# 06_Arduino_UNO.net
KiCad netlist of a schematic drawn in Altium Designer
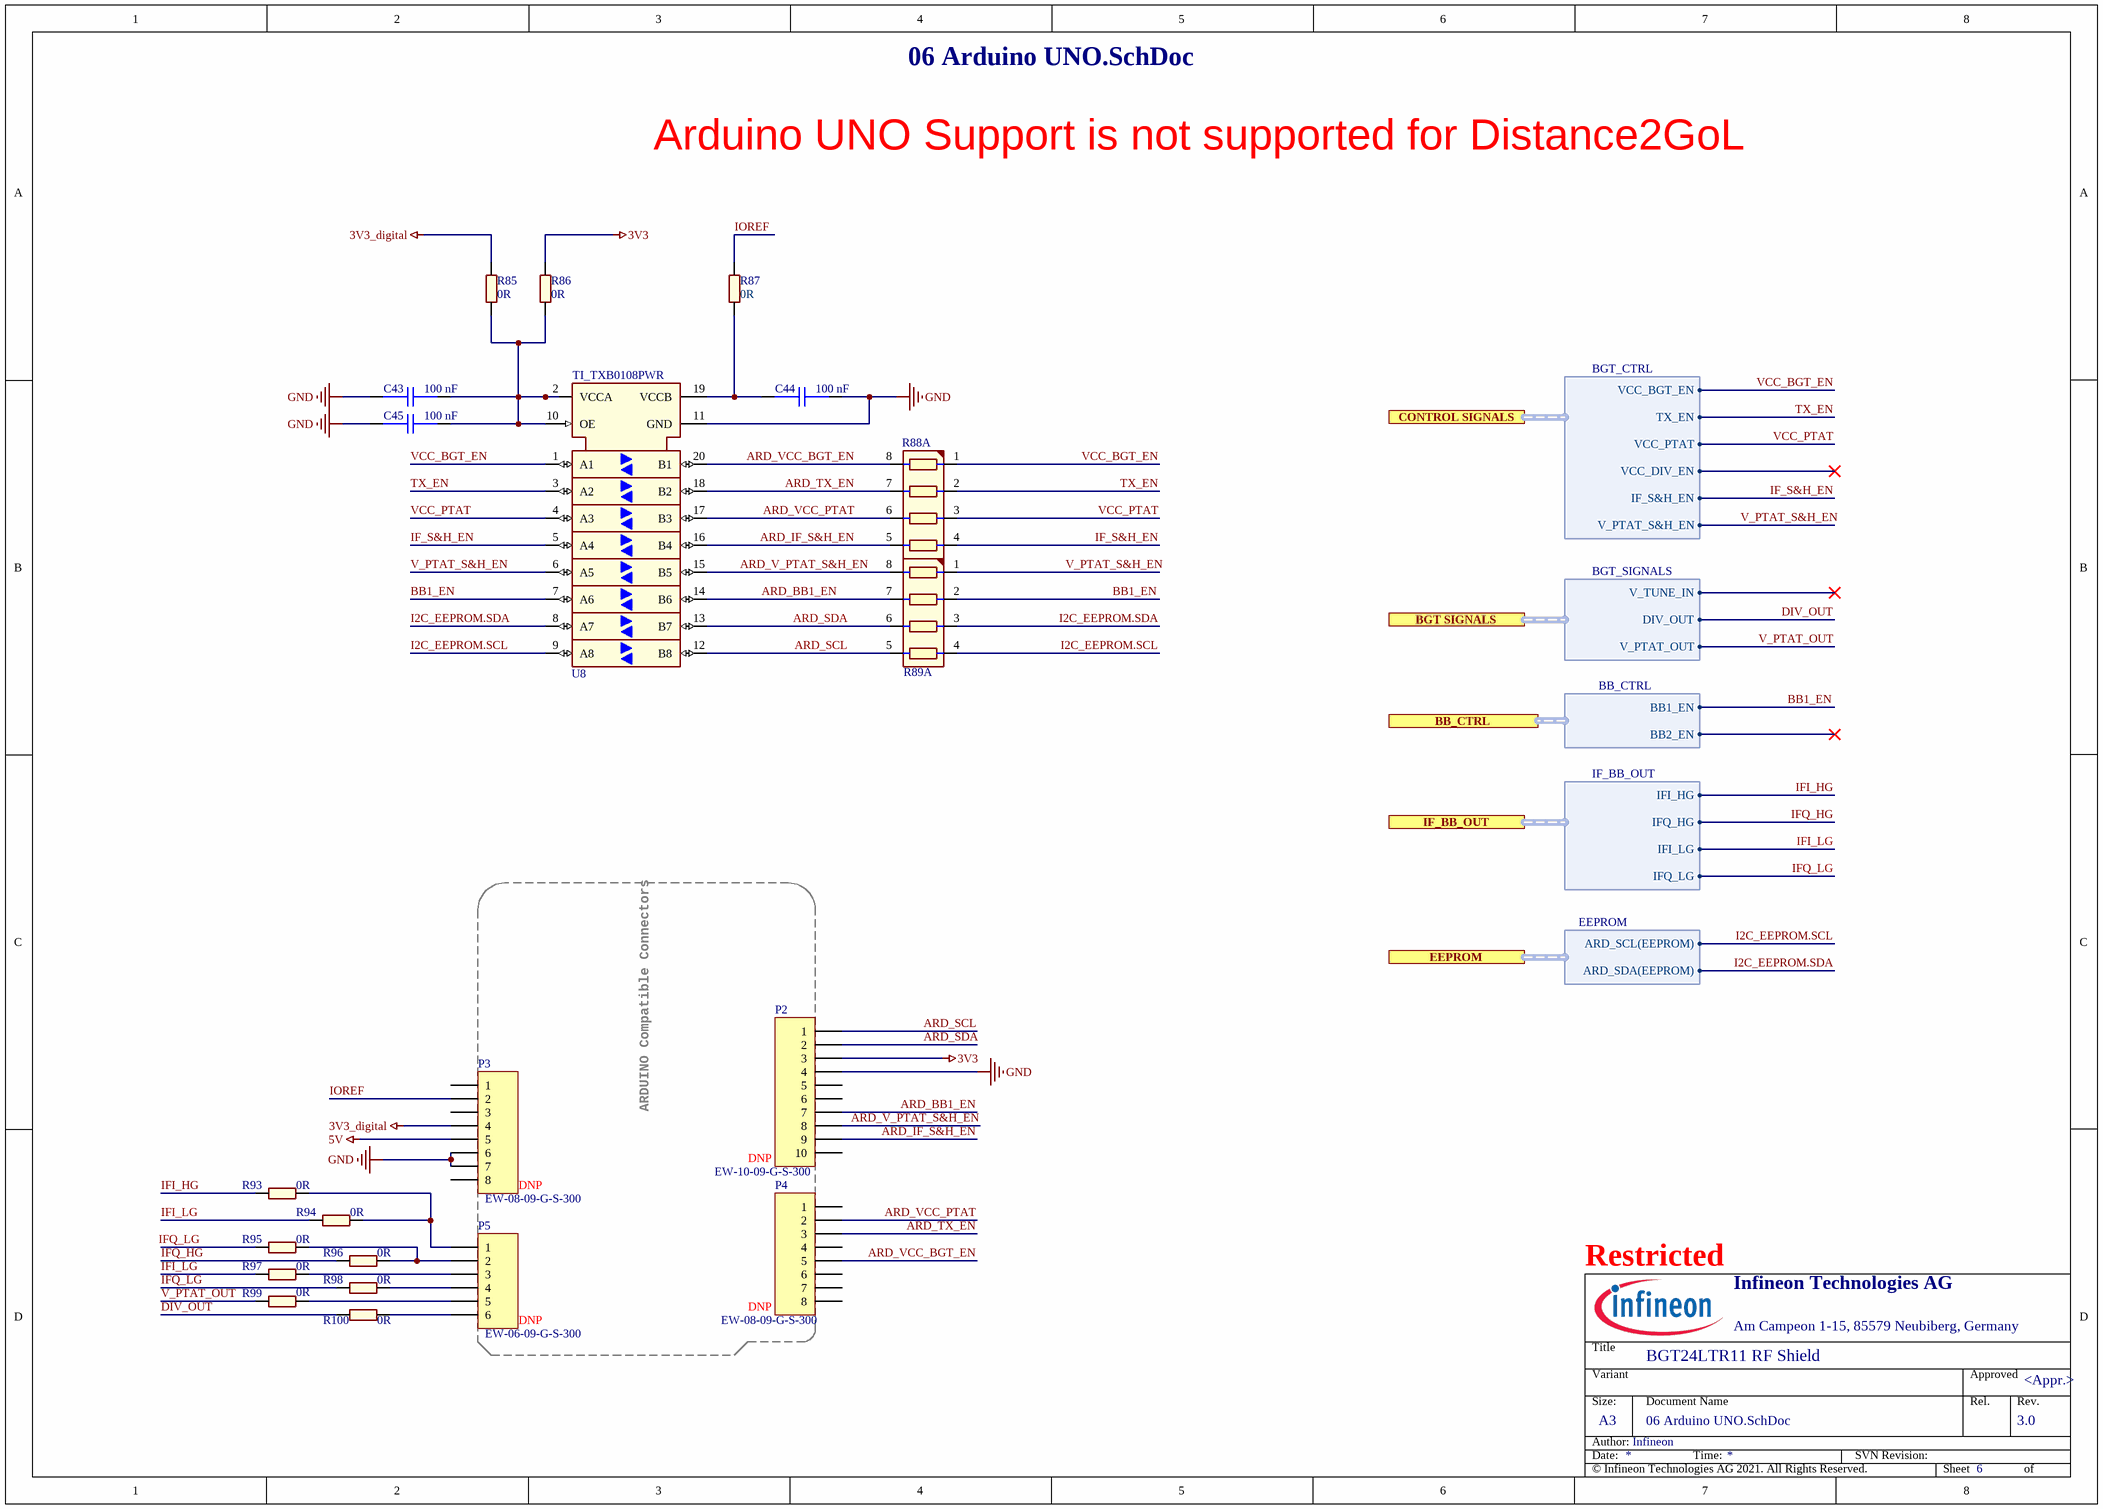
[diagram p0: 06 Arduino UNO.SchDoc]

(export (version "E")
  (design (tool "Eeschema 10.0.6"))
  (components
    (comp (ref "C43")
      (value "100 nF")
      (footprint "CAPC1005X55N-0_2")
      (description "General Purpose Surface Mount Ceramic Capacitor")
      (fields (field (name "PARTNUMBER") "CAP01010597") (field (name "VOLTAGE") "16Vdc"))
      (libsource (lib "DB_External_Capacitor") (part "c_std_a"))
    )
    (comp (ref "C44")
      (value "100 nF")
      (footprint "CAPC1005X55N-0_2")
      (description "General Purpose Surface Mount Ceramic Capacitor")
      (fields (field (name "PARTNUMBER") "CAP01010597") (field (name "VOLTAGE") "16Vdc"))
      (libsource (lib "DB_External_Capacitor") (part "c_std_a"))
    )
    (comp (ref "C45")
      (value "100 nF")
      (footprint "CAPC1005X55N-0_2")
      (description "General Purpose Surface Mount Ceramic Capacitor")
      (fields (field (name "PARTNUMBER") "CAP01010597") (field (name "VOLTAGE") "16Vdc"))
      (libsource (lib "DB_External_Capacitor") (part "c_std_a"))
    )
    (comp (ref "P2")
      (value "DNP")
      (footprint "HDR1X10_Plug - DNP")
      (description "Header, 10-Pin, 10mm Height, EW-10-09-G-S-300")
      (fields
        (field (name "MANUFACTURER PART NUMBER") "EW-10-09-G-S-300")
        (field (name "MANUFACTURER") "Samtec")
        (field (name "PUBLISHER") "Altium Limited")
      )
      (libsource (lib "Miscellaneous Connectors") (part "Header 10"))
    )
    (comp (ref "P3")
      (value "DNP")
      (footprint "HDR1X8_Plug - DNP")
      (description "Header, 8-Pin 10mm Height, EW-08-09-G-S-300")
      (fields
        (field (name "MANUFACTURER PART NUMBER") "EW-08-09-G-S-300")
        (field (name "MANUFACTURER") "Samtec")
        (field (name "PUBLISHER") "Altium Limited")
      )
      (libsource (lib "") (part "Header 8_1"))
    )
    (comp (ref "P4")
      (value "DNP")
      (footprint "HDR1X8_Plug - DNP")
      (description "Header, 8-Pin 10mm Height, EW-08-09-G-S-300")
      (fields
        (field (name "MANUFACTURER PART NUMBER") "EW-08-09-G-S-300")
        (field (name "MANUFACTURER") "Samtec")
        (field (name "PUBLISHER") "Altium Limited")
      )
      (libsource (lib "Miscellaneous Connectors") (part "Header 8"))
    )
    (comp (ref "P5")
      (value "DNP")
      (footprint "HDR1X6_Plug - DNP")
      (description "Header, 6-Pin, 10mm Height, EW-06-09-G-S-300")
      (fields
        (field (name "MANUFACTURER PART NUMBER") "EW-06-09-G-S-300")
        (field (name "MANUFACTURER") "Samtec")
        (field (name "PUBLISHER") "Altium Limited")
      )
      (libsource (lib "Miscellaneous Connectors") (part "Header 6"))
    )
    (comp (ref "R85")
      (value "0R")
      (footprint "RESC1005X40N_2")
      (description "0R/50V/20mOhm")
      (fields (field (name "PARTNUMBER") "RES01800000") (field (name "POWER") "1.5A"))
      (libsource (lib "") (part "r_std_a_2"))
    )
    (comp (ref "R86")
      (value "0R")
      (footprint "RESC1005X40N_2")
      (description "0R/50V/20mOhm")
      (fields (field (name "PARTNUMBER") "RES01800000") (field (name "POWER") "1.5A"))
      (libsource (lib "") (part "r_std_a_3"))
    )
    (comp (ref "R87")
      (value "0R")
      (footprint "RESC1005X40N_2")
      (description "0R/50V/20mOhm")
      (fields (field (name "PARTNUMBER") "RES01800000") (field (name "POWER") "1.5A"))
      (libsource (lib "") (part "r_std_a_3"))
    )
    (comp (ref "R88")
      (value "DNP")
      (footprint "RESCAX50P100X200X45-8N - DNP")
      (description "Thick Film Chip Resistor Array")
      (fields (field (name "MANUFACTURER") "Panasonic"))
      (libsource (lib "BGT24LTR11 RF-Shield Board V0.2") (part "RES-ARY-STD-08P_00000029"))
    )
    (comp (ref "R89")
      (value "DNP")
      (footprint "RESCAX50P100X200X45-8N - DNP")
      (description "Thick Film Chip Resistor Array")
      (fields (field (name "MANUFACTURER") "Panasonic"))
      (libsource (lib "BGT24LTR11 RF-Shield Board V0.2") (part "RES-ARY-STD-08P_00000029"))
    )
    (comp (ref "R93")
      (value "0R")
      (footprint "RESC1005X40N_2")
      (description "0R/50V/20mOhm")
      (fields (field (name "PARTNUMBER") "RES01800000") (field (name "POWER") "1.5A"))
      (libsource (lib "DB_External_Resistor") (part "r_std_a"))
    )
    (comp (ref "R94")
      (value "0R")
      (footprint "RESC1005X40N_2")
      (description "0R/50V/20mOhm")
      (fields (field (name "PARTNUMBER") "RES01800000") (field (name "POWER") "1.5A"))
      (libsource (lib "DB_External_Resistor") (part "r_std_a"))
    )
    (comp (ref "R95")
      (value "0R")
      (footprint "RESC1005X40N_2")
      (description "0R/50V/20mOhm")
      (fields (field (name "PARTNUMBER") "RES01800000") (field (name "POWER") "1.5A"))
      (libsource (lib "DB_External_Resistor") (part "r_std_a"))
    )
    (comp (ref "R96")
      (value "0R")
      (footprint "RESC1005X40N_2")
      (description "0R/50V/20mOhm")
      (fields (field (name "PARTNUMBER") "RES01800000") (field (name "POWER") "1.5A"))
      (libsource (lib "DB_External_Resistor") (part "r_std_a"))
    )
    (comp (ref "R97")
      (value "0R")
      (footprint "RESC1005X40N_2")
      (description "0R/50V/20mOhm")
      (fields (field (name "PARTNUMBER") "RES01800000") (field (name "POWER") "1.5A"))
      (libsource (lib "DB_External_Resistor") (part "r_std_a"))
    )
    (comp (ref "R98")
      (value "0R")
      (footprint "RESC1005X40N_2")
      (description "0R/50V/20mOhm")
      (fields (field (name "PARTNUMBER") "RES01800000") (field (name "POWER") "1.5A"))
      (libsource (lib "DB_External_Resistor") (part "r_std_a"))
    )
    (comp (ref "R99")
      (value "0R")
      (footprint "RESC1005X40N_2")
      (description "0R/50V/20mOhm")
      (fields (field (name "PARTNUMBER") "RES01800000") (field (name "POWER") "1.5A"))
      (libsource (lib "DB_External_Resistor") (part "r_std_a"))
    )
    (comp (ref "R100")
      (value "0R")
      (footprint "RESC1005X40N_2")
      (description "0R/50V/20mOhm")
      (fields (field (name "PARTNUMBER") "RES01800000") (field (name "POWER") "1.5A"))
      (libsource (lib "") (part "r_std_a_1"))
    )
    (comp (ref "U8")
      (value "DNP")
      (footprint "SOP65P640X120-20N - DNP")
      (description "TI_TXB0108PWR")
      (fields
        (field (name "PARTNUMBER") "IC02600537")
        (field (name "COMPONENTNAME") "TI_TXB0108PWR")
        (field (name "MANUFACTURERPARTNUMBER") "TXB0108PWR")
      )
      (libsource (lib "DB_External_IC") (part "TXB0108PWR"))
    )
  )
  (nets
    (net (code "6") (name "/ARD_BB1_EN") (class "Default")
      (node (ref "P2") (pin "7") (pinfunction "7_7") (pintype "passive"))
      (node (ref "R89") (pin "7") (pinfunction "7_7") (pintype "passive"))
      (node (ref "U8") (pin "14") (pinfunction "B6_14") (pintype "bidirectional"))
    )
    (net (code "7") (name "/ARD_IF_S&H_EN") (class "Default")
      (node (ref "P2") (pin "9") (pinfunction "9_9") (pintype "passive"))
      (node (ref "R88") (pin "5") (pinfunction "5_5") (pintype "passive"))
      (node (ref "U8") (pin "16") (pinfunction "B4_16") (pintype "bidirectional"))
    )
    (net (code "8") (name "/ARD_SCL") (class "Default")
      (node (ref "P2") (pin "1") (pinfunction "1_1") (pintype "passive"))
      (node (ref "R89") (pin "5") (pinfunction "5_5") (pintype "passive"))
      (node (ref "U8") (pin "12") (pinfunction "B8_12") (pintype "bidirectional"))
    )
    (net (code "9") (name "/ARD_SDA") (class "Default")
      (node (ref "P2") (pin "2") (pinfunction "2_2") (pintype "passive"))
      (node (ref "R89") (pin "6") (pinfunction "6_6") (pintype "passive"))
      (node (ref "U8") (pin "13") (pinfunction "B7_13") (pintype "bidirectional"))
    )
    (net (code "10") (name "/ARD_TX_EN") (class "Default")
      (node (ref "P4") (pin "3") (pinfunction "3_3") (pintype "passive"))
      (node (ref "R88") (pin "7") (pinfunction "7_7") (pintype "passive"))
      (node (ref "U8") (pin "18") (pinfunction "B2_18") (pintype "bidirectional"))
    )
    (net (code "11") (name "/ARD_VCC_BGT_EN") (class "Default")
      (node (ref "P4") (pin "5") (pinfunction "5_5") (pintype "passive"))
      (node (ref "R88") (pin "8") (pinfunction "8_8") (pintype "passive"))
      (node (ref "U8") (pin "20") (pinfunction "B1_20") (pintype "bidirectional"))
    )
    (net (code "12") (name "/ARD_VCC_PTAT") (class "Default")
      (node (ref "P4") (pin "2") (pinfunction "2_2") (pintype "passive"))
      (node (ref "R88") (pin "6") (pinfunction "6_6") (pintype "passive"))
      (node (ref "U8") (pin "17") (pinfunction "B3_17") (pintype "bidirectional"))
    )
    (net (code "13") (name "/ARD_V_PTAT_S&H_EN") (class "Default")
      (node (ref "P2") (pin "8") (pinfunction "8_8") (pintype "passive"))
      (node (ref "R89") (pin "8") (pinfunction "8_8") (pintype "passive"))
      (node (ref "U8") (pin "15") (pinfunction "B5_15") (pintype "bidirectional"))
    )
    (net (code "14") (name "/BB1_EN") (class "Default")
      (node (ref "R89") (pin "2") (pinfunction "2_2") (pintype "passive"))
      (node (ref "U8") (pin "7") (pinfunction "A6_7") (pintype "bidirectional"))
    )
    (net (code "15") (name "/DIV_OUT") (class "Default")
      (node (ref "R100") (pin "2") (pinfunction "2_2") (pintype "passive"))
    )
    (net (code "16") (name "/I2C_EEPROM.SCL") (class "Default")
      (node (ref "R89") (pin "4") (pinfunction "4_4") (pintype "passive"))
      (node (ref "U8") (pin "9") (pinfunction "A8_9") (pintype "bidirectional"))
    )
    (net (code "17") (name "/I2C_EEPROM.SDA") (class "Default")
      (node (ref "R89") (pin "3") (pinfunction "3_3") (pintype "passive"))
      (node (ref "U8") (pin "8") (pinfunction "A7_8") (pintype "bidirectional"))
    )
    (net (code "18") (name "/IFI_HG") (class "Default")
      (node (ref "R93") (pin "2") (pinfunction "2_2") (pintype "passive"))
    )
    (net (code "19") (name "/IFI_LG") (class "Default")
      (node (ref "R94") (pin "2") (pinfunction "2_2") (pintype "passive"))
      (node (ref "R97") (pin "2") (pinfunction "2_2") (pintype "passive"))
    )
    (net (code "20") (name "/IFQ_HG") (class "Default")
      (node (ref "R96") (pin "2") (pinfunction "2_2") (pintype "passive"))
    )
    (net (code "21") (name "/IFQ_LG") (class "Default")
      (node (ref "R95") (pin "2") (pinfunction "2_2") (pintype "passive"))
      (node (ref "R98") (pin "2") (pinfunction "2_2") (pintype "passive"))
    )
    (net (code "22") (name "/IF_S&H_EN") (class "Default")
      (node (ref "R88") (pin "4") (pinfunction "4_4") (pintype "passive"))
      (node (ref "U8") (pin "5") (pinfunction "A4_5") (pintype "bidirectional"))
    )
    (net (code "23") (name "/IOREF") (class "Default")
      (node (ref "P3") (pin "2") (pinfunction "2_2") (pintype "passive"))
      (node (ref "R87") (pin "2") (pinfunction "2_2") (pintype "passive"))
    )
    (net (code "24") (name "/TX_EN") (class "Default")
      (node (ref "R88") (pin "2") (pinfunction "2_2") (pintype "passive"))
      (node (ref "U8") (pin "3") (pinfunction "A2_3") (pintype "bidirectional"))
    )
    (net (code "25") (name "/VCC_BGT_EN") (class "Default")
      (node (ref "R88") (pin "1") (pinfunction "1_1") (pintype "passive"))
      (node (ref "U8") (pin "1") (pinfunction "A1_1") (pintype "bidirectional"))
    )
    (net (code "26") (name "/VCC_PTAT") (class "Default")
      (node (ref "R88") (pin "3") (pinfunction "3_3") (pintype "passive"))
      (node (ref "U8") (pin "4") (pinfunction "A3_4") (pintype "bidirectional"))
    )
    (net (code "27") (name "/V_PTAT_OUT") (class "Default")
      (node (ref "R99") (pin "2") (pinfunction "2_2") (pintype "passive"))
    )
    (net (code "28") (name "/V_PTAT_S&H_EN") (class "Default")
      (node (ref "R89") (pin "1") (pinfunction "1_1") (pintype "passive"))
      (node (ref "U8") (pin "6") (pinfunction "A5_6") (pintype "bidirectional"))
    )
    (net (code "34") (name "3V3") (class "Default")
      (node (ref "P2") (pin "3") (pinfunction "3_3") (pintype "passive"))
      (node (ref "R86") (pin "2") (pinfunction "2_2") (pintype "passive"))
    )
    (net (code "35") (name "3V3_digital") (class "Default")
      (node (ref "P3") (pin "4") (pinfunction "4_4") (pintype "passive"))
      (node (ref "R85") (pin "2") (pinfunction "2_2") (pintype "passive"))
    )
    (net (code "36") (name "5V") (class "Default")
      (node (ref "P3") (pin "5") (pinfunction "5_5") (pintype "passive"))
    )
    (net (code "37") (name "GND") (class "Default")
      (node (ref "C43") (pin "1") (pinfunction "1_1") (pintype "passive"))
      (node (ref "C44") (pin "2") (pinfunction "2_2") (pintype "passive"))
      (node (ref "C45") (pin "1") (pinfunction "1_1") (pintype "passive"))
      (node (ref "P2") (pin "4") (pinfunction "4_4") (pintype "passive"))
      (node (ref "P3") (pin "6") (pinfunction "6_6") (pintype "passive"))
      (node (ref "P3") (pin "7") (pinfunction "7_7") (pintype "passive"))
      (node (ref "U8") (pin "11") (pinfunction "GND_11") (pintype "power_in"))
    )
    (net (code "38") (name "Net-(P5-Pad1)") (class "Default")
      (node (ref "P5") (pin "1") (pinfunction "1_1") (pintype "passive"))
      (node (ref "R93") (pin "1") (pinfunction "1_1") (pintype "passive"))
      (node (ref "R94") (pin "1") (pinfunction "1_1") (pintype "passive"))
    )
    (net (code "39") (name "Net-(P5-Pad2)") (class "Default")
      (node (ref "P5") (pin "2") (pinfunction "2_2") (pintype "passive"))
      (node (ref "R95") (pin "1") (pinfunction "1_1") (pintype "passive"))
      (node (ref "R96") (pin "1") (pinfunction "1_1") (pintype "passive"))
    )
    (net (code "40") (name "Net-(P5-Pad3)") (class "Default")
      (node (ref "P5") (pin "3") (pinfunction "3_3") (pintype "passive"))
      (node (ref "R97") (pin "1") (pinfunction "1_1") (pintype "passive"))
    )
    (net (code "41") (name "Net-(P5-Pad4)") (class "Default")
      (node (ref "P5") (pin "4") (pinfunction "4_4") (pintype "passive"))
      (node (ref "R98") (pin "1") (pinfunction "1_1") (pintype "passive"))
    )
    (net (code "42") (name "Net-(P5-Pad5)") (class "Default")
      (node (ref "P5") (pin "5") (pinfunction "5_5") (pintype "passive"))
      (node (ref "R99") (pin "1") (pinfunction "1_1") (pintype "passive"))
    )
    (net (code "43") (name "Net-(P5-Pad6)") (class "Default")
      (node (ref "P5") (pin "6") (pinfunction "6_6") (pintype "passive"))
      (node (ref "R100") (pin "1") (pinfunction "1_1") (pintype "passive"))
    )
    (net (code "44") (name "Net-(U8-OE)") (class "Default")
      (node (ref "C43") (pin "2") (pinfunction "2_2") (pintype "passive"))
      (node (ref "C45") (pin "2") (pinfunction "2_2") (pintype "passive"))
      (node (ref "R85") (pin "1") (pinfunction "1_1") (pintype "passive"))
      (node (ref "R86") (pin "1") (pinfunction "1_1") (pintype "passive"))
      (node (ref "U8") (pin "10") (pinfunction "OE_10") (pintype "input"))
      (node (ref "U8") (pin "2") (pinfunction "VCCA_2") (pintype "power_in"))
    )
    (net (code "45") (name "Net-(U8-VCCB)") (class "Default")
      (node (ref "C44") (pin "1") (pinfunction "1_1") (pintype "passive"))
      (node (ref "R87") (pin "1") (pinfunction "1_1") (pintype "passive"))
      (node (ref "U8") (pin "19") (pinfunction "VCCB_19") (pintype "power_in"))
    )
    (net (code "46") (name "unconnected-(P2-Pad5)") (class "Default")
      (node (ref "P2") (pin "5") (pinfunction "5_5") (pintype "passive"))
    )
    (net (code "47") (name "unconnected-(P2-Pad6)") (class "Default")
      (node (ref "P2") (pin "6") (pinfunction "6_6") (pintype "passive"))
    )
    (net (code "48") (name "unconnected-(P2-Pad10)") (class "Default")
      (node (ref "P2") (pin "10") (pinfunction "10_10") (pintype "passive"))
    )
    (net (code "49") (name "unconnected-(P3-Pad1)") (class "Default")
      (node (ref "P3") (pin "1") (pinfunction "1_1") (pintype "passive"))
    )
    (net (code "50") (name "unconnected-(P3-Pad3)") (class "Default")
      (node (ref "P3") (pin "3") (pinfunction "3_3") (pintype "passive"))
    )
    (net (code "51") (name "unconnected-(P3-Pad8)") (class "Default")
      (node (ref "P3") (pin "8") (pinfunction "8_8") (pintype "passive"))
    )
    (net (code "52") (name "unconnected-(P4-Pad1)") (class "Default")
      (node (ref "P4") (pin "1") (pinfunction "1_1") (pintype "passive"))
    )
    (net (code "53") (name "unconnected-(P4-Pad4)") (class "Default")
      (node (ref "P4") (pin "4") (pinfunction "4_4") (pintype "passive"))
    )
    (net (code "54") (name "unconnected-(P4-Pad6)") (class "Default")
      (node (ref "P4") (pin "6") (pinfunction "6_6") (pintype "passive"))
    )
    (net (code "55") (name "unconnected-(P4-Pad7)") (class "Default")
      (node (ref "P4") (pin "7") (pinfunction "7_7") (pintype "passive"))
    )
    (net (code "56") (name "unconnected-(P4-Pad8)") (class "Default")
      (node (ref "P4") (pin "8") (pinfunction "8_8") (pintype "passive"))
    )
  )
)
